# USBA_Term.net
KiCad netlist of a schematic drawn in Altium Designer
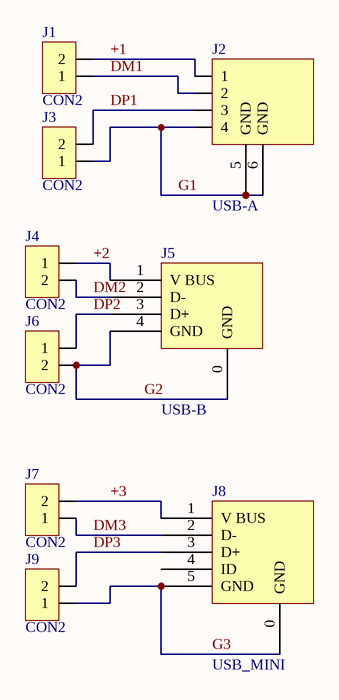
[diagram p0: USBA_Term.SchDoc]

(export (version "E")
  (design (tool "Eeschema 10.0.6"))
  (components
    (comp (ref "J1") (value "CON2") (footprint "TERMS5mm2") (libsource (lib "") (part "CON2_1")))
    (comp (ref "J2") (value "USB-A") (footprint "USB_A") (libsource (lib "DEVICE") (part "USB-A")))
    (comp (ref "J3") (value "CON2") (footprint "TERMS5mm2") (libsource (lib "") (part "CON2_1")))
    (comp (ref "J4") (value "CON2") (footprint "TERMS5mm2") (libsource (lib "DEVICE") (part "CON2")))
    (comp (ref "J5") (value "USB-B") (footprint "USB_B") (libsource (lib "DEVICE") (part "USB-B")))
    (comp (ref "J6") (value "CON2") (footprint "TERMS5mm2") (libsource (lib "DEVICE") (part "CON2")))
    (comp (ref "J7") (value "CON2") (footprint "TERMS5mm2") (libsource (lib "") (part "CON2_1")))
    (comp (ref "J8") (value "USB_MINI") (footprint "USB_MINI_B") (libsource (lib "DEVICE") (part "USB_MINI")))
    (comp (ref "J9") (value "CON2") (footprint "TERMS5mm2") (libsource (lib "") (part "CON2_1")))
  )
  (nets
    (net (code "1") (name "/+1") (class "Default")
      (node (ref "J1") (pin "2") (pinfunction "2_2") (pintype "passive"))
      (node (ref "J2") (pin "1") (pinfunction "1_1") (pintype "passive"))
    )
    (net (code "2") (name "/+2") (class "Default")
      (node (ref "J4") (pin "1") (pinfunction "1_1") (pintype "passive"))
      (node (ref "J5") (pin "1") (pinfunction "V_BUS_1") (pintype "passive"))
    )
    (net (code "3") (name "/+3") (class "Default")
      (node (ref "J7") (pin "2") (pinfunction "2_2") (pintype "passive"))
      (node (ref "J8") (pin "1") (pinfunction "V_BUS_1") (pintype "passive"))
    )
    (net (code "4") (name "/DM1") (class "Default")
      (node (ref "J1") (pin "1") (pinfunction "1_1") (pintype "passive"))
      (node (ref "J2") (pin "2") (pinfunction "2_2") (pintype "passive"))
    )
    (net (code "5") (name "/DM2") (class "Default")
      (node (ref "J4") (pin "2") (pinfunction "2_2") (pintype "passive"))
      (node (ref "J5") (pin "2") (pinfunction "D-_2") (pintype "passive"))
    )
    (net (code "6") (name "/DM3") (class "Default")
      (node (ref "J7") (pin "1") (pinfunction "1_1") (pintype "passive"))
      (node (ref "J8") (pin "2") (pinfunction "D-_2") (pintype "passive"))
    )
    (net (code "7") (name "/DP1") (class "Default")
      (node (ref "J2") (pin "3") (pinfunction "3_3") (pintype "passive"))
      (node (ref "J3") (pin "2") (pinfunction "2_2") (pintype "passive"))
    )
    (net (code "8") (name "/DP2") (class "Default")
      (node (ref "J5") (pin "3") (pinfunction "D+_3") (pintype "passive"))
      (node (ref "J6") (pin "1") (pinfunction "1_1") (pintype "passive"))
    )
    (net (code "9") (name "/DP3") (class "Default")
      (node (ref "J8") (pin "3") (pinfunction "D+_3") (pintype "passive"))
      (node (ref "J9") (pin "2") (pinfunction "2_2") (pintype "passive"))
    )
    (net (code "10") (name "/G1") (class "Default")
      (node (ref "J2") (pin "4") (pinfunction "4_4") (pintype "passive"))
      (node (ref "J2") (pin "5") (pinfunction "GND_5") (pintype "power_in"))
      (node (ref "J2") (pin "6") (pinfunction "GND_6") (pintype "power_in"))
      (node (ref "J3") (pin "1") (pinfunction "1_1") (pintype "passive"))
    )
    (net (code "11") (name "/G2") (class "Default")
      (node (ref "J5") (pin "0") (pinfunction "GND_0") (pintype "power_in"))
      (node (ref "J5") (pin "4") (pinfunction "GND_4") (pintype "passive"))
      (node (ref "J6") (pin "2") (pinfunction "2_2") (pintype "passive"))
    )
    (net (code "12") (name "/G3") (class "Default")
      (node (ref "J8") (pin "0") (pinfunction "GND_0") (pintype "power_in"))
      (node (ref "J8") (pin "5") (pinfunction "GND_5") (pintype "passive"))
      (node (ref "J9") (pin "1") (pinfunction "1_1") (pintype "passive"))
    )
    (net (code "13") (name "unconnected-(J8-ID-Pad4)") (class "Default")
      (node (ref "J8") (pin "4") (pinfunction "ID_4") (pintype "passive"))
    )
  )
)
